# Adafruit_5in_HDMI_Backpack.net
KiCad netlist of a schematic drawn in EAGLE
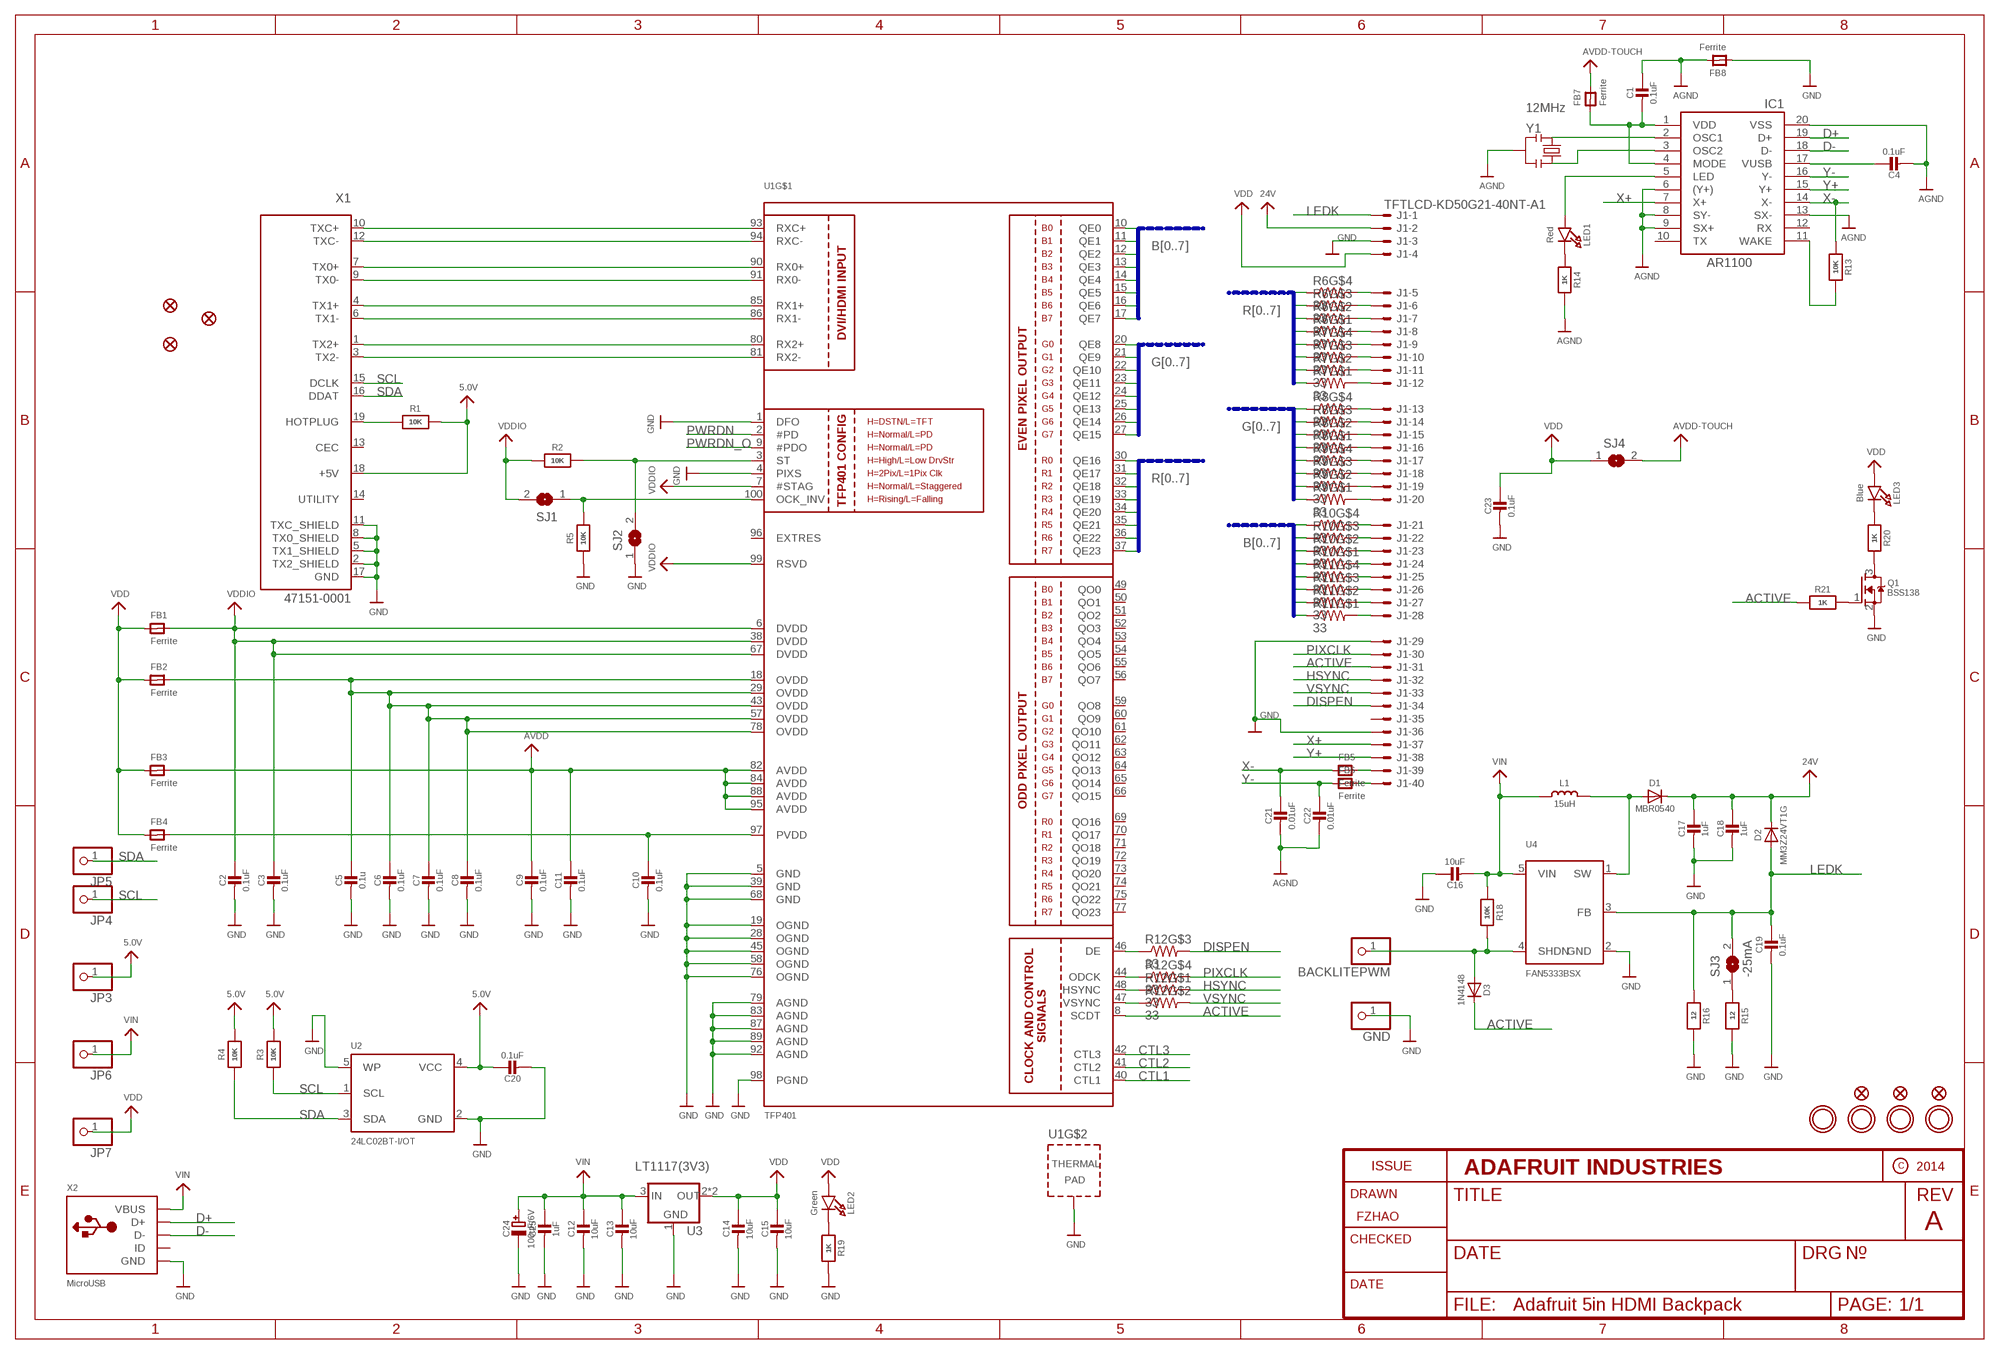
[diagram p0: schematic, sheet 1]

(export (version "E")
  (design (tool "Eeschema 10.0.6"))
  (components
    (comp (ref "BACKLITEPWM")
      (value "HEADER-1X1-SMD_MASKHELD_2X2MM")
      (footprint "eagle-import:1X01_SMD_MASKHELD_2X2MM")
      (libsource (lib "eagle-import") (part "HEADER-1X1-SMD_MASKHELD_2X2MM"))
    )
    (comp (ref "C1")
      (value "0.1uF")
      (footprint "eagle-import:0805-NO")
      (libsource (lib "eagle-import") (part "CAP_CERAMIC0805-NOOUTLINE"))
    )
    (comp (ref "C2")
      (value "0.1uF")
      (footprint "eagle-import:0805-NO")
      (libsource (lib "eagle-import") (part "CAP_CERAMIC0805-NOOUTLINE"))
    )
    (comp (ref "C3")
      (value "0.1uF")
      (footprint "eagle-import:0805-NO")
      (libsource (lib "eagle-import") (part "CAP_CERAMIC0805-NOOUTLINE"))
    )
    (comp (ref "C4")
      (value "0.1uF")
      (footprint "eagle-import:_0805MP")
      (libsource (lib "eagle-import") (part "CAP_CERAMIC_0805MP"))
    )
    (comp (ref "C5")
      (value "0.1u")
      (footprint "eagle-import:0805-NO")
      (libsource (lib "eagle-import") (part "CAP_CERAMIC0805-NOOUTLINE"))
    )
    (comp (ref "C6")
      (value "0.1uF")
      (footprint "eagle-import:_0805MP")
      (libsource (lib "eagle-import") (part "CAP_CERAMIC_0805MP"))
    )
    (comp (ref "C7")
      (value "0.1uF")
      (footprint "eagle-import:0805-NO")
      (libsource (lib "eagle-import") (part "CAP_CERAMIC0805-NOOUTLINE"))
    )
    (comp (ref "C8")
      (value "0.1uF")
      (footprint "eagle-import:0805-NO")
      (libsource (lib "eagle-import") (part "CAP_CERAMIC0805-NOOUTLINE"))
    )
    (comp (ref "C9")
      (value "0.1uF")
      (footprint "eagle-import:0805-NO")
      (libsource (lib "eagle-import") (part "CAP_CERAMIC0805-NOOUTLINE"))
    )
    (comp (ref "C10")
      (value "0.1uF")
      (footprint "eagle-import:0805-NO")
      (libsource (lib "eagle-import") (part "CAP_CERAMIC0805-NOOUTLINE"))
    )
    (comp (ref "C11")
      (value "0.1uF")
      (footprint "eagle-import:0805-NO")
      (libsource (lib "eagle-import") (part "CAP_CERAMIC0805-NOOUTLINE"))
    )
    (comp (ref "C12")
      (value "10uF")
      (footprint "eagle-import:0805-NO")
      (libsource (lib "eagle-import") (part "CAP_CERAMIC0805-NOOUTLINE"))
    )
    (comp (ref "C13")
      (value "10uF")
      (footprint "eagle-import:0805-NO")
      (libsource (lib "eagle-import") (part "CAP_CERAMIC0805-NOOUTLINE"))
    )
    (comp (ref "C14")
      (value "10uF")
      (footprint "eagle-import:0805-NO")
      (libsource (lib "eagle-import") (part "CAP_CERAMIC0805-NOOUTLINE"))
    )
    (comp (ref "C15")
      (value "10uF")
      (footprint "eagle-import:0805-NO")
      (libsource (lib "eagle-import") (part "CAP_CERAMIC0805-NOOUTLINE"))
    )
    (comp (ref "C16")
      (value "10uF")
      (footprint "eagle-import:0805-NO")
      (libsource (lib "eagle-import") (part "CAP_CERAMIC0805-NOOUTLINE"))
    )
    (comp (ref "C17")
      (value "1uF")
      (footprint "eagle-import:0805-NO")
      (libsource (lib "eagle-import") (part "CAP_CERAMIC0805-NOOUTLINE"))
    )
    (comp (ref "C18")
      (value "1uF")
      (footprint "eagle-import:0805-NO")
      (libsource (lib "eagle-import") (part "CAP_CERAMIC0805-NOOUTLINE"))
    )
    (comp (ref "C19")
      (value "0.1uF")
      (footprint "eagle-import:0805-NO")
      (libsource (lib "eagle-import") (part "CAP_CERAMIC0805-NOOUTLINE"))
    )
    (comp (ref "C20")
      (value "0.1uF")
      (footprint "eagle-import:0805-NO")
      (libsource (lib "eagle-import") (part "CAP_CERAMIC0805-NOOUTLINE"))
    )
    (comp (ref "C21")
      (value "0.01uF")
      (footprint "eagle-import:0805-NO")
      (libsource (lib "eagle-import") (part "CAP_CERAMIC0805-NOOUTLINE"))
    )
    (comp (ref "C22")
      (value "0.01uF")
      (footprint "eagle-import:0805-NO")
      (libsource (lib "eagle-import") (part "CAP_CERAMIC0805-NOOUTLINE"))
    )
    (comp (ref "C23")
      (value "0.1uF")
      (footprint "eagle-import:0805-NO")
      (libsource (lib "eagle-import") (part "CAP_CERAMIC0805-NOOUTLINE"))
    )
    (comp (ref "C24")
      (value "100uF/6V")
      (footprint "eagle-import:PANASONIC_C")
      (libsource (lib "eagle-import") (part "CAP_ELECTROLYTICPANASONIC_C"))
    )
    (comp (ref "C25")
      (value "1uF")
      (footprint "eagle-import:0805-NO")
      (libsource (lib "eagle-import") (part "CAP_CERAMIC0805-NOOUTLINE"))
    )
    (comp (ref "D1")
      (value "MBR0540")
      (footprint "eagle-import:SOD-123")
      (libsource (lib "eagle-import") (part "DIODESOD-123"))
    )
    (comp (ref "D2")
      (value "MM3Z24VT1G")
      (footprint "eagle-import:SMADIODE")
      (libsource (lib "eagle-import") (part "DIODESMA"))
    )
    (comp (ref "D3")
      (value "1N4148")
      (footprint "eagle-import:SOD-323")
      (libsource (lib "eagle-import") (part "DIODESOD-323"))
    )
    (comp (ref "FB1")
      (value "Ferrite")
      (footprint "eagle-import:_0805MP")
      (libsource (lib "eagle-import") (part "FERRITE_0805MP"))
    )
    (comp (ref "FB2")
      (value "Ferrite")
      (footprint "eagle-import:_0805MP")
      (libsource (lib "eagle-import") (part "FERRITE_0805MP"))
    )
    (comp (ref "FB3")
      (value "Ferrite")
      (footprint "eagle-import:_0805MP")
      (libsource (lib "eagle-import") (part "FERRITE_0805MP"))
    )
    (comp (ref "FB4")
      (value "Ferrite")
      (footprint "eagle-import:_0805MP")
      (libsource (lib "eagle-import") (part "FERRITE_0805MP"))
    )
    (comp (ref "FB5")
      (value "Ferrite")
      (footprint "eagle-import:_0805MP")
      (libsource (lib "eagle-import") (part "FERRITE_0805MP"))
    )
    (comp (ref "FB6")
      (value "Ferrite")
      (footprint "eagle-import:_0805MP")
      (libsource (lib "eagle-import") (part "FERRITE_0805MP"))
    )
    (comp (ref "FB7")
      (value "Ferrite")
      (footprint "eagle-import:_0805MP")
      (libsource (lib "eagle-import") (part "FERRITE_0805MP"))
    )
    (comp (ref "FB8")
      (value "Ferrite")
      (footprint "eagle-import:_0805MP")
      (libsource (lib "eagle-import") (part "FERRITE_0805MP"))
    )
    (comp (ref "FID1")
      (value "FIDUCIAL\"\"")
      (footprint "eagle-import:FIDUCIAL_1MM")
      (libsource (lib "eagle-import") (part "FIDUCIAL{dblquote}{dblquote}"))
    )
    (comp (ref "FID2")
      (value "FIDUCIAL\"\"")
      (footprint "eagle-import:FIDUCIAL_1MM")
      (libsource (lib "eagle-import") (part "FIDUCIAL{dblquote}{dblquote}"))
    )
    (comp (ref "FID3")
      (value "FIDUCIAL\"\"")
      (footprint "eagle-import:FIDUCIAL_1MM")
      (libsource (lib "eagle-import") (part "FIDUCIAL{dblquote}{dblquote}"))
    )
    (comp (ref "FID4")
      (value "FIDUCIAL\"\"")
      (footprint "eagle-import:FIDUCIAL_1MM")
      (libsource (lib "eagle-import") (part "FIDUCIAL{dblquote}{dblquote}"))
    )
    (comp (ref "FID5")
      (value "FIDUCIAL\"\"")
      (footprint "eagle-import:FIDUCIAL_1MM")
      (libsource (lib "eagle-import") (part "FIDUCIAL{dblquote}{dblquote}"))
    )
    (comp (ref "FID6")
      (value "FIDUCIAL\"\"")
      (footprint "eagle-import:FIDUCIAL_1MM")
      (libsource (lib "eagle-import") (part "FIDUCIAL{dblquote}{dblquote}"))
    )
    (comp (ref "GND")
      (value "HEADER-1X1-SMD_MASKHELD_2X2MM")
      (footprint "eagle-import:1X01_SMD_MASKHELD_2X2MM")
      (libsource (lib "eagle-import") (part "HEADER-1X1-SMD_MASKHELD_2X2MM"))
    )
    (comp (ref "IC1")
      (value "AR1100")
      (footprint "eagle-import:TSSOP20-5.3MMBODY")
      (libsource (lib "eagle-import") (part "AR1100_SSOP"))
    )
    (comp (ref "J1")
      (value "TFTLCD-KD50G21-40NT-A1")
      (footprint "eagle-import:TFTLCD-KD50G21-40NT-A1")
      (libsource (lib "eagle-import") (part "TFTLCD-KD50G21-40NT-A1"))
    )
    (comp (ref "JP3")
      (value "HEADER-1X1-SMD_MASKHELD_2X2MM")
      (footprint "eagle-import:1X01_SMD_MASKHELD_2X2MM")
      (libsource (lib "eagle-import") (part "HEADER-1X1-SMD_MASKHELD_2X2MM"))
    )
    (comp (ref "JP4")
      (value "HEADER-1X1-SMD_MASKHELD_2X2MM")
      (footprint "eagle-import:1X01_SMD_MASKHELD_2X2MM")
      (libsource (lib "eagle-import") (part "HEADER-1X1-SMD_MASKHELD_2X2MM"))
    )
    (comp (ref "JP5")
      (value "HEADER-1X1-SMD_MASKHELD_2X2MM")
      (footprint "eagle-import:1X01_SMD_MASKHELD_2X2MM")
      (libsource (lib "eagle-import") (part "HEADER-1X1-SMD_MASKHELD_2X2MM"))
    )
    (comp (ref "JP6")
      (value "HEADER-1X1-SMD_MASKHELD_2X2MM")
      (footprint "eagle-import:1X01_SMD_MASKHELD_2X2MM")
      (libsource (lib "eagle-import") (part "HEADER-1X1-SMD_MASKHELD_2X2MM"))
    )
    (comp (ref "JP7")
      (value "HEADER-1X1-SMD_MASKHELD_2X2MM")
      (footprint "eagle-import:1X01_SMD_MASKHELD_2X2MM")
      (libsource (lib "eagle-import") (part "HEADER-1X1-SMD_MASKHELD_2X2MM"))
    )
    (comp (ref "L1")
      (value "15uH")
      (footprint "eagle-import:INDUCTOR_5X5MM_NR5040_NOTHERMALS")
      (libsource (lib "eagle-import") (part "INDUCTORNR5040"))
    )
    (comp (ref "LED1")
      (value "Red")
      (footprint "eagle-import:CHIPLED_0805_NOOUTLINE")
      (libsource (lib "eagle-import") (part "LED0805_NOOUTLINE"))
    )
    (comp (ref "LED2")
      (value "Green")
      (footprint "eagle-import:CHIPLED_0805_NOOUTLINE")
      (libsource (lib "eagle-import") (part "LED0805_NOOUTLINE"))
    )
    (comp (ref "LED3")
      (value "Blue")
      (footprint "eagle-import:CHIPLED_0805_NOOUTLINE")
      (libsource (lib "eagle-import") (part "LED0805_NOOUTLINE"))
    )
    (comp (ref "Q1")
      (value "BSS138")
      (footprint "eagle-import:SOT23-WIDE")
      (libsource (lib "eagle-import") (part "MOSFET-NWIDE"))
    )
    (comp (ref "R1")
      (value "10K")
      (footprint "eagle-import:0805-NO")
      (libsource (lib "eagle-import") (part "RESISTOR0805_NOOUTLINE"))
    )
    (comp (ref "R2")
      (value "10K")
      (footprint "eagle-import:_0805MP")
      (libsource (lib "eagle-import") (part "RESISTOR_0805MP"))
    )
    (comp (ref "R3")
      (value "10K")
      (footprint "eagle-import:0805-NO")
      (libsource (lib "eagle-import") (part "RESISTOR0805_NOOUTLINE"))
    )
    (comp (ref "R4")
      (value "10K")
      (footprint "eagle-import:0805-NO")
      (libsource (lib "eagle-import") (part "RESISTOR0805_NOOUTLINE"))
    )
    (comp (ref "R5")
      (value "10K")
      (footprint "eagle-import:_0805MP")
      (libsource (lib "eagle-import") (part "RESISTOR_0805MP"))
    )
    (comp (ref "R6")
      (value "33")
      (footprint "eagle-import:RESPACK_4X0603")
      (libsource (lib "eagle-import") (part "RESISTOR_4PACK_US"))
    )
    (comp (ref "R7")
      (value "33")
      (footprint "eagle-import:RESPACK_4X0603")
      (libsource (lib "eagle-import") (part "RESISTOR_4PACK_US"))
    )
    (comp (ref "R8")
      (value "33")
      (footprint "eagle-import:RESPACK_4X0603")
      (libsource (lib "eagle-import") (part "RESISTOR_4PACK_US"))
    )
    (comp (ref "R9")
      (value "33")
      (footprint "eagle-import:RESPACK_4X0603")
      (libsource (lib "eagle-import") (part "RESISTOR_4PACK_US"))
    )
    (comp (ref "R10")
      (value "33")
      (footprint "eagle-import:RESPACK_4X0603")
      (libsource (lib "eagle-import") (part "RESISTOR_4PACK_US"))
    )
    (comp (ref "R11")
      (value "33")
      (footprint "eagle-import:RESPACK_4X0603")
      (libsource (lib "eagle-import") (part "RESISTOR_4PACK_US"))
    )
    (comp (ref "R12")
      (value "33")
      (footprint "eagle-import:RESPACK_4X0603")
      (libsource (lib "eagle-import") (part "RESISTOR_4PACK_US"))
    )
    (comp (ref "R13")
      (value "10K")
      (footprint "eagle-import:0805-NO")
      (libsource (lib "eagle-import") (part "RESISTOR0805_NOOUTLINE"))
    )
    (comp (ref "R14")
      (value "1K")
      (footprint "eagle-import:0805-NO")
      (libsource (lib "eagle-import") (part "RESISTOR0805_NOOUTLINE"))
    )
    (comp (ref "R15")
      (value "12")
      (footprint "eagle-import:0805-NO")
      (libsource (lib "eagle-import") (part "RESISTOR0805_NOOUTLINE"))
    )
    (comp (ref "R16")
      (value "12")
      (footprint "eagle-import:0805-NO")
      (libsource (lib "eagle-import") (part "RESISTOR0805_NOOUTLINE"))
    )
    (comp (ref "R18")
      (value "10K")
      (footprint "eagle-import:0805-NO")
      (libsource (lib "eagle-import") (part "RESISTOR0805_NOOUTLINE"))
    )
    (comp (ref "R19")
      (value "1K")
      (footprint "eagle-import:0805-NO")
      (libsource (lib "eagle-import") (part "RESISTOR0805_NOOUTLINE"))
    )
    (comp (ref "R20")
      (value "1K")
      (footprint "eagle-import:0805-NO")
      (libsource (lib "eagle-import") (part "RESISTOR0805_NOOUTLINE"))
    )
    (comp (ref "R21")
      (value "1K")
      (footprint "eagle-import:0805-NO")
      (libsource (lib "eagle-import") (part "RESISTOR0805_NOOUTLINE"))
    )
    (comp (ref "SJ1")
      (value "SOLDERJUMPER")
      (footprint "eagle-import:SOLDERJUMPER_ARROW_NOPASTE")
      (libsource (lib "eagle-import") (part "SOLDERJUMPER"))
    )
    (comp (ref "SJ2")
      (value "SOLDERJUMPER")
      (footprint "eagle-import:SOLDERJUMPER_ARROW_NOPASTE")
      (fields (field (name "BOM") "EXCLUDE"))
      (libsource (lib "eagle-import") (part "SOLDERJUMPER"))
    )
    (comp (ref "SJ3")
      (value "-25mA")
      (footprint "eagle-import:SOLDERJUMPER_CLOSEDWIRE")
      (libsource (lib "eagle-import") (part "SOLDERJUMPERCLOSED"))
    )
    (comp (ref "SJ4")
      (value "SOLDERJUMPERCLOSED")
      (footprint "eagle-import:SOLDERJUMPER_CLOSEDWIRE")
      (libsource (lib "eagle-import") (part "SOLDERJUMPERCLOSED"))
    )
    (comp (ref "U$31")
      (value "MOUNTINGHOLE3.0")
      (footprint "eagle-import:MOUNTINGHOLE_3.0_PLATED")
      (libsource (lib "eagle-import") (part "MOUNTINGHOLE3.0"))
    )
    (comp (ref "U$32")
      (value "MOUNTINGHOLE3.0")
      (footprint "eagle-import:MOUNTINGHOLE_3.0_PLATED")
      (libsource (lib "eagle-import") (part "MOUNTINGHOLE3.0"))
    )
    (comp (ref "U$33")
      (value "MOUNTINGHOLE3.0")
      (footprint "eagle-import:MOUNTINGHOLE_3.0_PLATED")
      (libsource (lib "eagle-import") (part "MOUNTINGHOLE3.0"))
    )
    (comp (ref "U$34")
      (value "MOUNTINGHOLE3.0")
      (footprint "eagle-import:MOUNTINGHOLE_3.0_PLATED")
      (libsource (lib "eagle-import") (part "MOUNTINGHOLE3.0"))
    )
    (comp (ref "U1")
      (value "TFP401")
      (footprint "eagle-import:S-PQFP-G100")
      (libsource (lib "eagle-import") (part "TFP401"))
    )
    (comp (ref "U2")
      (value "24LC02BT-I/OT")
      (footprint "eagle-import:SOT23-5")
      (libsource (lib "eagle-import") (part "EEPROM_I2C_MCP24AA32"))
    )
    (comp (ref "U3")
      (value "LT1117(3V3)")
      (footprint "eagle-import:SOT223-R")
      (libsource (lib "eagle-import") (part "VREG_SOT223"))
    )
    (comp (ref "U4")
      (value "FAN5333BSX")
      (footprint "eagle-import:SOT23-5")
      (libsource (lib "eagle-import") (part "VREG_FAN5331"))
    )
    (comp (ref "X1")
      (value "47151-0001")
      (footprint "eagle-import:HDMI_MOLEX_47151-0001_DIMLAYER")
      (libsource (lib "eagle-import") (part "HDMI_MOLEX_47151DIM"))
    )
    (comp (ref "X2")
      (value "MicroUSB")
      (footprint "eagle-import:4UCONN_20329")
      (libsource (lib "eagle-import") (part "USBMICRO_20329"))
    )
    (comp (ref "Y1")
      (value "12MHz")
      (footprint "eagle-import:RESONATOR-SMD")
      (libsource (lib "eagle-import") (part "RESONATORSMD"))
    )
  )
  (nets
    (net (code "1") (name "/ACTIVE") (class "Default")
      (node (ref "D3") (pin "C") (pinfunction "C_C") (pintype "passive"))
      (node (ref "J1") (pin "31") (pinfunction "MS_31") (pintype "passive"))
      (node (ref "R21") (pin "1") (pinfunction "1_1") (pintype "passive"))
      (node (ref "U1") (pin "8") (pinfunction "SCDT_8") (pintype "output"))
    )
    (net (code "2") (name "/B0") (class "Default")
      (node (ref "R10") (pin "4") (pinfunction "1_4") (pintype "passive"))
      (node (ref "U1") (pin "10") (pinfunction "QE0_10") (pintype "output"))
    )
    (net (code "3") (name "/B1") (class "Default")
      (node (ref "R10") (pin "3") (pinfunction "1_3") (pintype "passive"))
      (node (ref "U1") (pin "11") (pinfunction "QE1_11") (pintype "output"))
    )
    (net (code "4") (name "/B2") (class "Default")
      (node (ref "R10") (pin "2") (pinfunction "1_2") (pintype "passive"))
      (node (ref "U1") (pin "12") (pinfunction "QE2_12") (pintype "output"))
    )
    (net (code "5") (name "/B3") (class "Default")
      (node (ref "R10") (pin "1") (pinfunction "1_1") (pintype "passive"))
      (node (ref "U1") (pin "13") (pinfunction "QE3_13") (pintype "output"))
    )
    (net (code "6") (name "/B4") (class "Default")
      (node (ref "R11") (pin "4") (pinfunction "1_4") (pintype "passive"))
      (node (ref "U1") (pin "14") (pinfunction "QE4_14") (pintype "output"))
    )
    (net (code "7") (name "/B5") (class "Default")
      (node (ref "R11") (pin "3") (pinfunction "1_3") (pintype "passive"))
      (node (ref "U1") (pin "15") (pinfunction "QE5_15") (pintype "output"))
    )
    (net (code "8") (name "/B6") (class "Default")
      (node (ref "R11") (pin "2") (pinfunction "1_2") (pintype "passive"))
      (node (ref "U1") (pin "16") (pinfunction "QE6_16") (pintype "output"))
    )
    (net (code "9") (name "/B7") (class "Default")
      (node (ref "R11") (pin "1") (pinfunction "1_1") (pintype "passive"))
      (node (ref "U1") (pin "17") (pinfunction "QE7_17") (pintype "output"))
    )
    (net (code "11") (name "/CTL1") (class "Default")
      (node (ref "U1") (pin "40") (pinfunction "CTL1_40") (pintype "output"))
    )
    (net (code "12") (name "/CTL2") (class "Default")
      (node (ref "U1") (pin "41") (pinfunction "CTL2_41") (pintype "output"))
    )
    (net (code "13") (name "/CTL3") (class "Default")
      (node (ref "U1") (pin "42") (pinfunction "CTL3_42") (pintype "output"))
    )
    (net (code "14") (name "/D+") (class "Default")
      (node (ref "IC1") (pin "19") (pinfunction "D+_19") (pintype "bidirectional"))
      (node (ref "X2") (pin "D+") (pinfunction "D+_D+") (pintype "bidirectional"))
    )
    (net (code "15") (name "/D-") (class "Default")
      (node (ref "IC1") (pin "18") (pinfunction "D-_18") (pintype "bidirectional"))
      (node (ref "X2") (pin "D-") (pinfunction "D-_D-") (pintype "bidirectional"))
    )
    (net (code "16") (name "/DISPEN") (class "Default")
      (node (ref "J1") (pin "34") (pinfunction "MS_34") (pintype "passive"))
      (node (ref "R12") (pin "6") (pinfunction "2_6") (pintype "passive"))
    )
    (net (code "17") (name "/G0") (class "Default")
      (node (ref "R8") (pin "4") (pinfunction "1_4") (pintype "passive"))
      (node (ref "U1") (pin "20") (pinfunction "QE8_20") (pintype "output"))
    )
    (net (code "18") (name "/G1") (class "Default")
      (node (ref "R8") (pin "3") (pinfunction "1_3") (pintype "passive"))
      (node (ref "U1") (pin "21") (pinfunction "QE9_21") (pintype "output"))
    )
    (net (code "19") (name "/G2") (class "Default")
      (node (ref "R8") (pin "2") (pinfunction "1_2") (pintype "passive"))
      (node (ref "U1") (pin "22") (pinfunction "QE10_22") (pintype "output"))
    )
    (net (code "20") (name "/G3") (class "Default")
      (node (ref "R8") (pin "1") (pinfunction "1_1") (pintype "passive"))
      (node (ref "U1") (pin "23") (pinfunction "QE11_23") (pintype "output"))
    )
    (net (code "21") (name "/G4") (class "Default")
      (node (ref "R9") (pin "4") (pinfunction "1_4") (pintype "passive"))
      (node (ref "U1") (pin "24") (pinfunction "QE12_24") (pintype "output"))
    )
    (net (code "22") (name "/G5") (class "Default")
      (node (ref "R9") (pin "3") (pinfunction "1_3") (pintype "passive"))
      (node (ref "U1") (pin "25") (pinfunction "QE13_25") (pintype "output"))
    )
    (net (code "23") (name "/G6") (class "Default")
      (node (ref "R9") (pin "2") (pinfunction "1_2") (pintype "passive"))
      (node (ref "U1") (pin "26") (pinfunction "QE14_26") (pintype "output"))
    )
    (net (code "24") (name "/G7") (class "Default")
      (node (ref "R9") (pin "1") (pinfunction "1_1") (pintype "passive"))
      (node (ref "U1") (pin "27") (pinfunction "QE15_27") (pintype "output"))
    )
    (net (code "26") (name "/HSYNC") (class "Default")
      (node (ref "J1") (pin "32") (pinfunction "MS_32") (pintype "passive"))
      (node (ref "R12") (pin "8") (pinfunction "2_8") (pintype "passive"))
    )
    (net (code "27") (name "/LEDK") (class "Default")
      (node (ref "C19") (pin "1") (pinfunction "1_1") (pintype "passive"))
      (node (ref "D2") (pin "A") (pinfunction "A_A") (pintype "passive"))
      (node (ref "J1") (pin "1") (pinfunction "MSV_1") (pintype "passive"))
      (node (ref "R16") (pin "1") (pinfunction "1_1") (pintype "passive"))
      (node (ref "SJ3") (pin "2") (pinfunction "2_2") (pintype "passive"))
      (node (ref "U4") (pin "3") (pinfunction "FB_3") (pintype "bidirectional"))
    )
    (net (code "28") (name "/PIXCLK") (class "Default")
      (node (ref "J1") (pin "30") (pinfunction "MS_30") (pintype "passive"))
      (node (ref "R12") (pin "5") (pinfunction "2_5") (pintype "passive"))
    )
    (net (code "29") (name "/PWRDN") (class "Default")
      (node (ref "U1") (pin "2") (pinfunction "#PD_2") (pintype "input"))
    )
    (net (code "30") (name "/PWRDN_O") (class "Default")
      (node (ref "U1") (pin "9") (pinfunction "#PDO_9") (pintype "input"))
    )
    (net (code "31") (name "/R0") (class "Default")
      (node (ref "R6") (pin "4") (pinfunction "1_4") (pintype "passive"))
      (node (ref "U1") (pin "30") (pinfunction "QE16_30") (pintype "output"))
    )
    (net (code "32") (name "/R1") (class "Default")
      (node (ref "R6") (pin "3") (pinfunction "1_3") (pintype "passive"))
      (node (ref "U1") (pin "31") (pinfunction "QE17_31") (pintype "output"))
    )
    (net (code "33") (name "/R2") (class "Default")
      (node (ref "R6") (pin "2") (pinfunction "1_2") (pintype "passive"))
      (node (ref "U1") (pin "32") (pinfunction "QE18_32") (pintype "output"))
    )
    (net (code "34") (name "/R3") (class "Default")
      (node (ref "R6") (pin "1") (pinfunction "1_1") (pintype "passive"))
      (node (ref "U1") (pin "33") (pinfunction "QE19_33") (pintype "output"))
    )
    (net (code "35") (name "/R4") (class "Default")
      (node (ref "R7") (pin "4") (pinfunction "1_4") (pintype "passive"))
      (node (ref "U1") (pin "34") (pinfunction "QE20_34") (pintype "output"))
    )
    (net (code "36") (name "/R5") (class "Default")
      (node (ref "R7") (pin "3") (pinfunction "1_3") (pintype "passive"))
      (node (ref "U1") (pin "35") (pinfunction "QE21_35") (pintype "output"))
    )
    (net (code "37") (name "/R6") (class "Default")
      (node (ref "R7") (pin "2") (pinfunction "1_2") (pintype "passive"))
      (node (ref "U1") (pin "36") (pinfunction "QE22_36") (pintype "output"))
    )
    (net (code "38") (name "/R7") (class "Default")
      (node (ref "R7") (pin "1") (pinfunction "1_1") (pintype "passive"))
      (node (ref "U1") (pin "37") (pinfunction "QE23_37") (pintype "output"))
    )
    (net (code "40") (name "/SCL") (class "Default")
      (node (ref "JP4") (pin "1") (pinfunction "1_1") (pintype "passive"))
      (node (ref "R3") (pin "1") (pinfunction "1_1") (pintype "passive"))
      (node (ref "U2") (pin "1") (pinfunction "SCL_1") (pintype "bidirectional"))
      (node (ref "X1") (pin "15") (pinfunction "DCLK_15") (pintype "bidirectional"))
    )
    (net (code "41") (name "/SDA") (class "Default")
      (node (ref "JP5") (pin "1") (pinfunction "1_1") (pintype "passive"))
      (node (ref "R4") (pin "1") (pinfunction "1_1") (pintype "passive"))
      (node (ref "U2") (pin "3") (pinfunction "SDA_3") (pintype "bidirectional"))
      (node (ref "X1") (pin "16") (pinfunction "DDAT_16") (pintype "bidirectional"))
    )
    (net (code "42") (name "/VSYNC") (class "Default")
      (node (ref "J1") (pin "33") (pinfunction "MS_33") (pintype "passive"))
      (node (ref "R12") (pin "7") (pinfunction "2_7") (pintype "passive"))
    )
    (net (code "43") (name "/X+") (class "Default")
      (node (ref "IC1") (pin "7") (pinfunction "X+_7") (pintype "bidirectional"))
      (node (ref "J1") (pin "37") (pinfunction "MS_37") (pintype "passive"))
    )
    (net (code "44") (name "/X-") (class "Default")
      (node (ref "C21") (pin "1") (pinfunction "1_1") (pintype "passive"))
      (node (ref "FB5") (pin "1") (pinfunction "P$1_1") (pintype "passive"))
      (node (ref "IC1") (pin "14") (pinfunction "X-_14") (pintype "bidirectional"))
      (node (ref "R13") (pin "1") (pinfunction "1_1") (pintype "passive"))
    )
    (net (code "45") (name "/Y+") (class "Default")
      (node (ref "IC1") (pin "15") (pinfunction "Y+_15") (pintype "bidirectional"))
      (node (ref "J1") (pin "38") (pinfunction "MS_38") (pintype "passive"))
    )
    (net (code "46") (name "/Y-") (class "Default")
      (node (ref "C22") (pin "1") (pinfunction "1_1") (pintype "passive"))
      (node (ref "FB6") (pin "1") (pinfunction "P$1_1") (pintype "passive"))
      (node (ref "IC1") (pin "16") (pinfunction "Y-_16") (pintype "bidirectional"))
    )
    (net (code "47") (name "5.0V") (class "Default")
      (node (ref "C20") (pin "1") (pinfunction "1_1") (pintype "passive"))
      (node (ref "JP3") (pin "1") (pinfunction "1_1") (pintype "passive"))
      (node (ref "R1") (pin "2") (pinfunction "2_2") (pintype "passive"))
      (node (ref "R3") (pin "2") (pinfunction "2_2") (pintype "passive"))
      (node (ref "R4") (pin "2") (pinfunction "2_2") (pintype "passive"))
      (node (ref "U2") (pin "4") (pinfunction "VCC_4") (pintype "bidirectional"))
      (node (ref "X1") (pin "18") (pinfunction "+5V_18") (pintype "power_in"))
    )
    (net (code "48") (name "24V") (class "Default")
      (node (ref "C17") (pin "1") (pinfunction "1_1") (pintype "passive"))
      (node (ref "C18") (pin "1") (pinfunction "1_1") (pintype "passive"))
      (node (ref "D1") (pin "C") (pinfunction "C_C") (pintype "passive"))
      (node (ref "D2") (pin "C") (pinfunction "C_C") (pintype "passive"))
      (node (ref "J1") (pin "2") (pinfunction "MS_2") (pintype "passive"))
    )
    (net (code "49") (name "AGND") (class "Default")
      (node (ref "C1") (pin "1") (pinfunction "1_1") (pintype "passive"))
      (node (ref "C21") (pin "2") (pinfunction "2_2") (pintype "passive"))
      (node (ref "C22") (pin "2") (pinfunction "2_2") (pintype "passive"))
      (node (ref "C4") (pin "2") (pinfunction "2_2") (pintype "passive"))
      (node (ref "FB8") (pin "2") (pinfunction "P$2_2") (pintype "passive"))
      (node (ref "IC1") (pin "13") (pinfunction "SX-_13") (pintype "bidirectional"))
      (node (ref "IC1") (pin "20") (pinfunction "VSS_20") (pintype "power_in"))
      (node (ref "IC1") (pin "6") (pinfunction "(Y+)_6") (pintype "bidirectional"))
      (node (ref "IC1") (pin "8") (pinfunction "SY-_8") (pintype "bidirectional"))
      (node (ref "IC1") (pin "9") (pinfunction "SX+_9") (pintype "bidirectional"))
      (node (ref "R14") (pin "2") (pinfunction "2_2") (pintype "passive"))
      (node (ref "Y1") (pin "2") (pinfunction "2_2") (pintype "passive"))
    )
    (net (code "50") (name "AVDD") (class "Default")
      (node (ref "C11") (pin "1") (pinfunction "1_1") (pintype "passive"))
      (node (ref "C9") (pin "1") (pinfunction "1_1") (pintype "passive"))
      (node (ref "FB3") (pin "2") (pinfunction "P$2_2") (pintype "passive"))
      (node (ref "U1") (pin "82") (pinfunction "AVDD_82") (pintype "power_in"))
      (node (ref "U1") (pin "84") (pinfunction "AVDD_84") (pintype "power_in"))
      (node (ref "U1") (pin "88") (pinfunction "AVDD_88") (pintype "power_in"))
      (node (ref "U1") (pin "95") (pinfunction "AVDD_95") (pintype "power_in"))
    )
    (net (code "51") (name "AVDD-TOUCH") (class "Default")
      (node (ref "FB7") (pin "2") (pinfunction "P$2_2") (pintype "passive"))
      (node (ref "SJ4") (pin "2") (pinfunction "2_2") (pintype "passive"))
    )
    (net (code "52") (name "GND") (class "Default")
      (node (ref "C10") (pin "2") (pinfunction "2_2") (pintype "passive"))
      (node (ref "C11") (pin "2") (pinfunction "2_2") (pintype "passive"))
      (node (ref "C12") (pin "2") (pinfunction "2_2") (pintype "passive"))
      (node (ref "C13") (pin "2") (pinfunction "2_2") (pintype "passive"))
      (node (ref "C14") (pin "2") (pinfunction "2_2") (pintype "passive"))
      (node (ref "C15") (pin "2") (pinfunction "2_2") (pintype "passive"))
      (node (ref "C16") (pin "1") (pinfunction "1_1") (pintype "passive"))
      (node (ref "C17") (pin "2") (pinfunction "2_2") (pintype "passive"))
      (node (ref "C18") (pin "2") (pinfunction "2_2") (pintype "passive"))
      (node (ref "C19") (pin "2") (pinfunction "2_2") (pintype "passive"))
      (node (ref "C2") (pin "2") (pinfunction "2_2") (pintype "passive"))
      (node (ref "C20") (pin "2") (pinfunction "2_2") (pintype "passive"))
      (node (ref "C23") (pin "2") (pinfunction "2_2") (pintype "passive"))
      (node (ref "C24") (pin "-") (pinfunction "-_-") (pintype "passive"))
      (node (ref "C25") (pin "2") (pinfunction "2_2") (pintype "passive"))
      (node (ref "C3") (pin "2") (pinfunction "2_2") (pintype "passive"))
      (node (ref "C5") (pin "2") (pinfunction "2_2") (pintype "passive"))
      (node (ref "C6") (pin "2") (pinfunction "2_2") (pintype "passive"))
      (node (ref "C7") (pin "2") (pinfunction "2_2") (pintype "passive"))
      (node (ref "C8") (pin "2") (pinfunction "2_2") (pintype "passive"))
      (node (ref "C9") (pin "2") (pinfunction "2_2") (pintype "passive"))
      (node (ref "FB8") (pin "1") (pinfunction "P$1_1") (pintype "passive"))
      (node (ref "GND") (pin "1") (pinfunction "1_1") (pintype "passive"))
      (node (ref "J1") (pin "29") (pinfunction "MS_29") (pintype "passive"))
      (node (ref "J1") (pin "3") (pinfunction "MS_3") (pintype "passive"))
      (node (ref "J1") (pin "36") (pinfunction "MS_36") (pintype "passive"))
      (node (ref "Q1") (pin "2") (pinfunction "S_2") (pintype "bidirectional"))
      (node (ref "R15") (pin "2") (pinfunction "2_2") (pintype "passive"))
      (node (ref "R16") (pin "2") (pinfunction "2_2") (pintype "passive"))
      (node (ref "R19") (pin "2") (pinfunction "2_2") (pintype "passive"))
      (node (ref "R5") (pin "1") (pinfunction "1_1") (pintype "passive"))
      (node (ref "SJ2") (pin "1") (pinfunction "1_1") (pintype "passive"))
      (node (ref "U1") (pin "1") (pinfunction "DFO_1") (pintype "input"))
      (node (ref "U1") (pin "19") (pinfunction "OGND_19") (pintype "power_in"))
      (node (ref "U1") (pin "28") (pinfunction "OGND_28") (pintype "power_in"))
      (node (ref "U1") (pin "39") (pinfunction "GND_39") (pintype "power_in"))
      (node (ref "U1") (pin "4") (pinfunction "PIXS_4") (pintype "input"))
      (node (ref "U1") (pin "45") (pinfunction "OGND_45") (pintype "power_in"))
      (node (ref "U1") (pin "5") (pinfunction "GND_5") (pintype "power_in"))
      (node (ref "U1") (pin "58") (pinfunction "OGND_58") (pintype "power_in"))
      (node (ref "U1") (pin "68") (pinfunction "GND_68") (pintype "power_in"))
      (node (ref "U1") (pin "76") (pinfunction "OGND_76") (pintype "power_in"))
      (node (ref "U1") (pin "79") (pinfunction "AGND_79") (pintype "power_in"))
      (node (ref "U1") (pin "83") (pinfunction "AGND_83") (pintype "power_in"))
      (node (ref "U1") (pin "87") (pinfunction "AGND_87") (pintype "power_in"))
      (node (ref "U1") (pin "89") (pinfunction "AGND_89") (pintype "power_in"))
      (node (ref "U1") (pin "92") (pinfunction "AGND_92") (pintype "power_in"))
      (node (ref "U1") (pin "98") (pinfunction "PGND_98") (pintype "power_in"))
      (node (ref "U1") (pin "P$1") (pinfunction "TP_P$1") (pintype "power_in"))
      (node (ref "U1") (pin "P$10") (pinfunction "TP_P$10") (pintype "power_in"))
      (node (ref "U1") (pin "P$11") (pinfunction "TP_P$11") (pintype "power_in"))
      (node (ref "U1") (pin "P$12") (pinfunction "TP_P$12") (pintype "power_in"))
      (node (ref "U1") (pin "P$13") (pinfunction "TP_P$13") (pintype "power_in"))
      (node (ref "U1") (pin "P$14") (pinfunction "TP_P$14") (pintype "power_in"))
      (node (ref "U1") (pin "P$15") (pinfunction "TP_P$15") (pintype "power_in"))
      (node (ref "U1") (pin "P$16") (pinfunction "TP_P$16") (pintype "power_in"))
      (node (ref "U1") (pin "P$2") (pinfunction "TP_P$2") (pintype "power_in"))
      (node (ref "U1") (pin "P$3") (pinfunction "TP_P$3") (pintype "power_in"))
      (node (ref "U1") (pin "P$4") (pinfunction "TP_P$4") (pintype "power_in"))
      (node (ref "U1") (pin "P$5") (pinfunction "TP_P$5") (pintype "power_in"))
      (node (ref "U1") (pin "P$6") (pinfunction "TP_P$6") (pintype "power_in"))
      (node (ref "U1") (pin "P$7") (pinfunction "TP_P$7") (pintype "power_in"))
      (node (ref "U1") (pin "P$8") (pinfunction "TP_P$8") (pintype "power_in"))
      (node (ref "U1") (pin "P$9") (pinfunction "TP_P$9") (pintype "power_in"))
      (node (ref "U1") (pin "THERMAL") (pinfunction "TP_THERMAL") (pintype "power_in"))
      (node (ref "U2") (pin "2") (pinfunction "GND_2") (pintype "bidirectional"))
      (node (ref "U2") (pin "5") (pinfunction "WP_5") (pintype "bidirectional"))
      (node (ref "U3") (pin "1") (pinfunction "GND_1") (pintype "power_in"))
      (node (ref "U4") (pin "2") (pinfunction "GND_2") (pintype "bidirectional"))
      (node (ref "X1") (pin "11") (pinfunction "TXC_SHIELD_11") (pintype "power_in"))
      (node (ref "X1") (pin "17") (pinfunction "GND_17") (pintype "power_in"))
      (node (ref "X1") (pin "2") (pinfunction "TX2_SHIELD_2") (pintype "power_in"))
      (node (ref "X1") (pin "5") (pinfunction "TX1_SHIELD_5") (pintype "power_in"))
      (node (ref "X1") (pin "8") (pinfunction "TX0_SHIELD_8") (pintype "power_in"))
      (node (ref "X2") (pin "BASE@1") (pinfunction "GND_BASE@1") (pintype "power_in"))
      (node (ref "X2") (pin "BASE@2") (pinfunction "GND_BASE@2") (pintype "power_in"))
      (node (ref "X2") (pin "GND") (pinfunction "GND_GND") (pintype "power_in"))
      (node (ref "X2") (pin "SPRT@1") (pinfunction "GND_SPRT@1") (pintype "power_in"))
      (node (ref "X2") (pin "SPRT@2") (pinfunction "GND_SPRT@2") (pintype "power_in"))
      (node (ref "X2") (pin "SPRT@3") (pinfunction "GND_SPRT@3") (pintype "power_in"))
      (node (ref "X2") (pin "SPRT@4") (pinfunction "GND_SPRT@4") (pintype "power_in"))
    )
    (net (code "53") (name "Net-(FB2-P$2)") (class "Default")
      (node (ref "C5") (pin "1") (pinfunction "1_1") (pintype "passive"))
      (node (ref "C6") (pin "1") (pinfunction "1_1") (pintype "passive"))
      (node (ref "C7") (pin "1") (pinfunction "1_1") (pintype "passive"))
      (node (ref "C8") (pin "1") (pinfunction "1_1") (pintype "passive"))
      (node (ref "FB2") (pin "2") (pinfunction "P$2_2") (pintype "passive"))
      (node (ref "U1") (pin "18") (pinfunction "OVDD_18") (pintype "power_in"))
      (node (ref "U1") (pin "29") (pinfunction "OVDD_29") (pintype "power_in"))
      (node (ref "U1") (pin "43") (pinfunction "OVDD_43") (pintype "power_in"))
      (node (ref "U1") (pin "57") (pinfunction "OVDD_57") (pintype "power_in"))
      (node (ref "U1") (pin "78") (pinfunction "OVDD_78") (pintype "power_in"))
    )
    (net (code "54") (name "Net-(FB4-P$2)") (class "Default")
      (node (ref "C10") (pin "1") (pinfunction "1_1") (pintype "passive"))
      (node (ref "FB4") (pin "2") (pinfunction "P$2_2") (pintype "passive"))
      (node (ref "U1") (pin "97") (pinfunction "PVDD_97") (pintype "power_in"))
    )
    (net (code "55") (name "Net-(FB5-P$2)") (class "Default")
      (node (ref "FB5") (pin "2") (pinfunction "P$2_2") (pintype "passive"))
      (node (ref "J1") (pin "39") (pinfunction "MS_39") (pintype "passive"))
    )
    (net (code "56") (name "Net-(FB6-P$2)") (class "Default")
      (node (ref "FB6") (pin "2") (pinfunction "P$2_2") (pintype "passive"))
      (node (ref "J1") (pin "40") (pinfunction "MS_40") (pintype "passive"))
    )
    (net (code "57") (name "Net-(FB7-P$1)") (class "Default")
      (node (ref "C1") (pin "2") (pinfunction "2_2") (pintype "passive"))
      (node (ref "FB7") (pin "1") (pinfunction "P$1_1") (pintype "passive"))
      (node (ref "IC1") (pin "1") (pinfunction "VDD_1") (pintype "power_in"))
      (node (ref "IC1") (pin "4") (pinfunction "MODE_4") (pintype "input"))
    )
    (net (code "58") (name "Net-(IC1-LED)") (class "Default")
      (node (ref "IC1") (pin "5") (pinfunction "LED_5") (pintype "output"))
      (node (ref "LED1") (pin "A") (pinfunction "A_A") (pintype "passive"))
    )
    (net (code "59") (name "Net-(IC1-OSC1)") (class "Default")
      (node (ref "IC1") (pin "2") (pinfunction "OSC1_2") (pintype "passive"))
      (node (ref "Y1") (pin "1") (pinfunction "1_1") (pintype "passive"))
    )
    (net (code "60") (name "Net-(IC1-OSC2)") (class "Default")
      (node (ref "IC1") (pin "3") (pinfunction "OSC2_3") (pintype "passive"))
      (node (ref "Y1") (pin "3") (pinfunction "3_3") (pintype "passive"))
    )
    (net (code "61") (name "Net-(IC1-VUSB)") (class "Default")
      (node (ref "C4") (pin "1") (pinfunction "1_1") (pintype "passive"))
      (node (ref "IC1") (pin "17") (pinfunction "VUSB_17") (pintype "power_in"))
    )
    (net (code "62") (name "Net-(IC1-WAKE)") (class "Default")
      (node (ref "IC1") (pin "11") (pinfunction "WAKE_11") (pintype "input"))
      (node (ref "R13") (pin "2") (pinfunction "2_2") (pintype "passive"))
    )
    (net (code "63") (name "Net-(J1AJ-MS)") (class "Default")
      (node (ref "J1") (pin "5") (pinfunction "MS_5") (pintype "passive"))
      (node (ref "R6") (pin "5") (pinfunction "2_5") (pintype "passive"))
    )
    (net (code "64") (name "Net-(J1AK-MS)") (class "Default")
      (node (ref "J1") (pin "6") (pinfunction "MS_6") (pintype "passive"))
      (node (ref "R6") (pin "6") (pinfunction "2_6") (pintype "passive"))
    )
    (net (code "65") (name "Net-(J1AL-MS)") (class "Default")
      (node (ref "J1") (pin "7") (pinfunction "MS_7") (pintype "passive"))
      (node (ref "R6") (pin "7") (pinfunction "2_7") (pintype "passive"))
    )
    (net (code "66") (name "Net-(J1AM-MS)") (class "Default")
      (node (ref "J1") (pin "8") (pinfunction "MS_8") (pintype "passive"))
      (node (ref "R6") (pin "8") (pinfunction "2_8") (pintype "passive"))
    )
    (net (code "67") (name "Net-(J1AN-MS)") (class "Default")
      (node (ref "J1") (pin "9") (pinfunction "MS_9") (pintype "passive"))
      (node (ref "R7") (pin "5") (pinfunction "2_5") (pintype "passive"))
    )
    (net (code "68") (name "Net-(J1B-MS)") (class "Default")
      (node (ref "J1") (pin "10") (pinfunction "MS_10") (pintype "passive"))
      (node (ref "R7") (pin "6") (pinfunction "2_6") (pintype "passive"))
    )
    (net (code "69") (name "Net-(J1C-MS)") (class "Default")
      (node (ref "J1") (pin "11") (pinfunction "MS_11") (pintype "passive"))
      (node (ref "R7") (pin "7") (pinfunction "2_7") (pintype "passive"))
    )
    (net (code "70") (name "Net-(J1D-MS)") (class "Default")
      (node (ref "J1") (pin "12") (pinfunction "MS_12") (pintype "passive"))
      (node (ref "R7") (pin "8") (pinfunction "2_8") (pintype "passive"))
    )
    (net (code "71") (name "Net-(J1E-MS)") (class "Default")
      (node (ref "J1") (pin "13") (pinfunction "MS_13") (pintype "passive"))
      (node (ref "R8") (pin "5") (pinfunction "2_5") (pintype "passive"))
    )
    (net (code "72") (name "Net-(J1F-MS)") (class "Default")
      (node (ref "J1") (pin "14") (pinfunction "MS_14") (pintype "passive"))
      (node (ref "R8") (pin "6") (pinfunction "2_6") (pintype "passive"))
    )
    (net (code "73") (name "Net-(J1G-MS)") (class "Default")
      (node (ref "J1") (pin "15") (pinfunction "MS_15") (pintype "passive"))
      (node (ref "R8") (pin "7") (pinfunction "2_7") (pintype "passive"))
    )
    (net (code "74") (name "Net-(J1H-MS)") (class "Default")
      (node (ref "J1") (pin "16") (pinfunction "MS_16") (pintype "passive"))
      (node (ref "R8") (pin "8") (pinfunction "2_8") (pintype "passive"))
    )
    (net (code "75") (name "Net-(J1I-MS)") (class "Default")
      (node (ref "J1") (pin "17") (pinfunction "MS_17") (pintype "passive"))
      (node (ref "R9") (pin "5") (pinfunction "2_5") (pintype "passive"))
    )
    (net (code "76") (name "Net-(J1J-MS)") (class "Default")
      (node (ref "J1") (pin "18") (pinfunction "MS_18") (pintype "passive"))
      (node (ref "R9") (pin "6") (pinfunction "2_6") (pintype "passive"))
    )
    (net (code "77") (name "Net-(J1K-MS)") (class "Default")
      (node (ref "J1") (pin "19") (pinfunction "MS_19") (pintype "passive"))
      (node (ref "R9") (pin "7") (pinfunction "2_7") (pintype "passive"))
    )
    (net (code "78") (name "Net-(J1M-MS)") (class "Default")
      (node (ref "J1") (pin "20") (pinfunction "MS_20") (pintype "passive"))
      (node (ref "R9") (pin "8") (pinfunction "2_8") (pintype "passive"))
    )
    (net (code "79") (name "Net-(J1N-MS)") (class "Default")
      (node (ref "J1") (pin "21") (pinfunction "MS_21") (pintype "passive"))
      (node (ref "R10") (pin "5") (pinfunction "2_5") (pintype "passive"))
    )
    (net (code "80") (name "Net-(J1O-MS)") (class "Default")
      (node (ref "J1") (pin "22") (pinfunction "MS_22") (pintype "passive"))
      (node (ref "R10") (pin "6") (pinfunction "2_6") (pintype "passive"))
    )
    (net (code "81") (name "Net-(J1P-MS)") (class "Default")
      (node (ref "J1") (pin "23") (pinfunction "MS_23") (pintype "passive"))
      (node (ref "R10") (pin "7") (pinfunction "2_7") (pintype "passive"))
    )
    (net (code "82") (name "Net-(J1Q-MS)") (class "Default")
      (node (ref "J1") (pin "24") (pinfunction "MS_24") (pintype "passive"))
      (node (ref "R10") (pin "8") (pinfunction "2_8") (pintype "passive"))
    )
    (net (code "83") (name "Net-(J1R-MS)") (class "Default")
      (node (ref "J1") (pin "25") (pinfunction "MS_25") (pintype "passive"))
      (node (ref "R11") (pin "5") (pinfunction "2_5") (pintype "passive"))
    )
    (net (code "84") (name "Net-(J1S-MS)") (class "Default")
      (node (ref "J1") (pin "26") (pinfunction "MS_26") (pintype "passive"))
      (node (ref "R11") (pin "6") (pinfunction "2_6") (pintype "passive"))
    )
    (net (code "85") (name "Net-(J1T-MS)") (class "Default")
      (node (ref "J1") (pin "27") (pinfunction "MS_27") (pintype "passive"))
      (node (ref "R11") (pin "7") (pinfunction "2_7") (pintype "passive"))
    )
    (net (code "86") (name "Net-(J1U-MS)") (class "Default")
      (node (ref "J1") (pin "28") (pinfunction "MS_28") (pintype "passive"))
      (node (ref "R11") (pin "8") (pinfunction "2_8") (pintype "passive"))
    )
    (net (code "87") (name "Net-(L1-2)") (class "Default")
      (node (ref "D1") (pin "A") (pinfunction "A_A") (pintype "passive"))
      (node (ref "L1") (pin "P$2") (pinfunction "2_P$2") (pintype "passive"))
      (node (ref "U4") (pin "1") (pinfunction "SW_1") (pintype "bidirectional"))
    )
    (net (code "88") (name "Net-(LED1-PadC)") (class "Default")
      (node (ref "LED1") (pin "C") (pinfunction "C_C") (pintype "passive"))
      (node (ref "R14") (pin "1") (pinfunction "1_1") (pintype "passive"))
    )
    (net (code "89") (name "Net-(LED2-PadC)") (class "Default")
      (node (ref "LED2") (pin "C") (pinfunction "C_C") (pintype "passive"))
      (node (ref "R19") (pin "1") (pinfunction "1_1") (pintype "passive"))
    )
    (net (code "90") (name "Net-(LED3-PadC)") (class "Default")
      (node (ref "LED3") (pin "C") (pinfunction "C_C") (pintype "passive"))
      (node (ref "R20") (pin "1") (pinfunction "1_1") (pintype "passive"))
    )
    (net (code "91") (name "Net-(Q1-D)") (class "Default")
      (node (ref "Q1") (pin "3") (pinfunction "D_3") (pintype "bidirectional"))
      (node (ref "R20") (pin "2") (pinfunction "2_2") (pintype "passive"))
    )
    (net (code "92") (name "Net-(Q1-G)") (class "Default")
      (node (ref "Q1") (pin "1") (pinfunction "G_1") (pintype "bidirectional"))
      (node (ref "R21") (pin "2") (pinfunction "2_2") (pintype "passive"))
    )
    (net (code "93") (name "Net-(R12B-1)") (class "Default")
      (node (ref "R12") (pin "2") (pinfunction "1_2") (pintype "passive"))
      (node (ref "U1") (pin "47") (pinfunction "VSYNC_47") (pintype "output"))
    )
    (net (code "94") (name "Net-(R12C-1)") (class "Default")
      (node (ref "R12") (pin "3") (pinfunction "1_3") (pintype "passive"))
      (node (ref "U1") (pin "46") (pinfunction "DE_46") (pintype "output"))
    )
    (net (code "95") (name "Net-(R12D-1)") (class "Default")
      (node (ref "R12") (pin "4") (pinfunction "1_4") (pintype "passive"))
      (node (ref "U1") (pin "44") (pinfunction "ODCK_44") (pintype "output"))
    )
    (net (code "96") (name "Net-(R15-Pad1)") (class "Default")
      (node (ref "R15") (pin "1") (pinfunction "1_1") (pintype "passive"))
      (node (ref "SJ3") (pin "1") (pinfunction "1_1") (pintype "passive"))
    )
    (net (code "97") (name "Net-(U1A-HSYNC)") (class "Default")
      (node (ref "R12") (pin "1") (pinfunction "1_1") (pintype "passive"))
      (node (ref "U1") (pin "48") (pinfunction "HSYNC_48") (pintype "output"))
    )
    (net (code "98") (name "Net-(U1A-OCK_INV)") (class "Default")
      (node (ref "R5") (pin "2") (pinfunction "2_2") (pintype "passive"))
      (node (ref "SJ1") (pin "1") (pinfunction "1_1") (pintype "passive"))
      (node (ref "U1") (pin "100") (pinfunction "OCK_INV_100") (pintype "input"))
    )
    (net (code "99") (name "Net-(U1A-RX0+)") (class "Default")
      (node (ref "U1") (pin "90") (pinfunction "RX0+_90") (pintype "input"))
      (node (ref "X1") (pin "7") (pinfunction "TX0+_7") (pintype "bidirectional"))
    )
    (net (code "100") (name "Net-(U1A-RX0-)") (class "Default")
      (node (ref "U1") (pin "91") (pinfunction "RX0-_91") (pintype "input"))
      (node (ref "X1") (pin "9") (pinfunction "TX0-_9") (pintype "bidirectional"))
    )
    (net (code "101") (name "Net-(U1A-RX1+)") (class "Default")
      (node (ref "U1") (pin "85") (pinfunction "RX1+_85") (pintype "input"))
      (node (ref "X1") (pin "4") (pinfunction "TX1+_4") (pintype "bidirectional"))
    )
    (net (code "102") (name "Net-(U1A-RX1-)") (class "Default")
      (node (ref "U1") (pin "86") (pinfunction "RX1-_86") (pintype "input"))
      (node (ref "X1") (pin "6") (pinfunction "TX1-_6") (pintype "bidirectional"))
    )
    (net (code "103") (name "Net-(U1A-RX2+)") (class "Default")
      (node (ref "U1") (pin "80") (pinfunction "RX2+_80") (pintype "input"))
      (node (ref "X1") (pin "1") (pinfunction "TX2+_1") (pintype "bidirectional"))
    )
    (net (code "104") (name "Net-(U1A-RX2-)") (class "Default")
      (node (ref "U1") (pin "81") (pinfunction "RX2-_81") (pintype "input"))
      (node (ref "X1") (pin "3") (pinfunction "TX2-_3") (pintype "bidirectional"))
    )
    (net (code "105") (name "Net-(U1A-RXC+)") (class "Default")
      (node (ref "U1") (pin "93") (pinfunction "RXC+_93") (pintype "input"))
      (node (ref "X1") (pin "10") (pinfunction "TXC+_10") (pintype "bidirectional"))
    )
    (net (code "106") (name "Net-(U1A-RXC-)") (class "Default")
      (node (ref "U1") (pin "94") (pinfunction "RXC-_94") (pintype "input"))
      (node (ref "X1") (pin "12") (pinfunction "TXC-_12") (pintype "bidirectional"))
    )
    (net (code "107") (name "Net-(U1A-ST)") (class "Default")
      (node (ref "R2") (pin "2") (pinfunction "2_2") (pintype "passive"))
      (node (ref "SJ2") (pin "2") (pinfunction "2_2") (pintype "passive"))
      (node (ref "U1") (pin "3") (pinfunction "ST_3") (pintype "input"))
    )
    (net (code "108") (name "Net-(U4-SHDN)") (class "Default")
      (node (ref "BACKLITEPWM") (pin "1") (pinfunction "1_1") (pintype "passive"))
      (node (ref "D3") (pin "A") (pinfunction "A_A") (pintype "passive"))
      (node (ref "R18") (pin "2") (pinfunction "2_2") (pintype "passive"))
      (node (ref "U4") (pin "4") (pinfunction "SHDN_4") (pintype "bidirectional"))
    )
    (net (code "109") (name "Net-(X1A-HOTPLUG)") (class "Default")
      (node (ref "R1") (pin "1") (pinfunction "1_1") (pintype "passive"))
      (node (ref "X1") (pin "19") (pinfunction "HOTPLUG_19") (pintype "bidirectional"))
    )
    (net (code "110") (name "VDD") (class "Default")
      (node (ref "C14") (pin "1") (pinfunction "1_1") (pintype "passive"))
      (node (ref "C15") (pin "1") (pinfunction "1_1") (pintype "passive"))
      (node (ref "C23") (pin "1") (pinfunction "1_1") (pintype "passive"))
      (node (ref "FB1") (pin "1") (pinfunction "P$1_1") (pintype "passive"))
      (node (ref "FB2") (pin "1") (pinfunction "P$1_1") (pintype "passive"))
      (node (ref "FB3") (pin "1") (pinfunction "P$1_1") (pintype "passive"))
      (node (ref "FB4") (pin "1") (pinfunction "P$1_1") (pintype "passive"))
      (node (ref "J1") (pin "4") (pinfunction "MS_4") (pintype "passive"))
      (node (ref "JP7") (pin "1") (pinfunction "1_1") (pintype "passive"))
      (node (ref "LED2") (pin "A") (pinfunction "A_A") (pintype "passive"))
      (node (ref "LED3") (pin "A") (pinfunction "A_A") (pintype "passive"))
      (node (ref "SJ4") (pin "1") (pinfunction "1_1") (pintype "passive"))
      (node (ref "U3") (pin "2") (pinfunction "OUT_2") (pintype "power_in"))
      (node (ref "U3") (pin "4") (pinfunction "OUT_4") (pintype "power_in"))
    )
    (net (code "111") (name "VDDIO") (class "Default")
      (node (ref "C2") (pin "1") (pinfunction "1_1") (pintype "passive"))
      (node (ref "C3") (pin "1") (pinfunction "1_1") (pintype "passive"))
      (node (ref "FB1") (pin "2") (pinfunction "P$2_2") (pintype "passive"))
      (node (ref "R2") (pin "1") (pinfunction "1_1") (pintype "passive"))
      (node (ref "SJ1") (pin "2") (pinfunction "2_2") (pintype "passive"))
      (node (ref "U1") (pin "38") (pinfunction "DVDD_38") (pintype "power_in"))
      (node (ref "U1") (pin "6") (pinfunction "DVDD_6") (pintype "power_in"))
      (node (ref "U1") (pin "67") (pinfunction "DVDD_67") (pintype "power_in"))
      (node (ref "U1") (pin "7") (pinfunction "#STAG_7") (pintype "input"))
      (node (ref "U1") (pin "99") (pinfunction "RSVD_99") (pintype "input"))
    )
    (net (code "112") (name "VIN") (class "Default")
      (node (ref "C12") (pin "1") (pinfunction "1_1") (pintype "passive"))
      (node (ref "C13") (pin "1") (pinfunction "1_1") (pintype "passive"))
      (node (ref "C16") (pin "2") (pinfunction "2_2") (pintype "passive"))
      (node (ref "C24") (pin "+") (pinfunction "+_+") (pintype "passive"))
      (node (ref "C25") (pin "1") (pinfunction "1_1") (pintype "passive"))
      (node (ref "JP6") (pin "1") (pinfunction "1_1") (pintype "passive"))
      (node (ref "L1") (pin "P$1") (pinfunction "1_P$1") (pintype "passive"))
      (node (ref "R18") (pin "1") (pinfunction "1_1") (pintype "passive"))
      (node (ref "U3") (pin "3") (pinfunction "IN_3") (pintype "power_in"))
      (node (ref "U4") (pin "5") (pinfunction "VIN_5") (pintype "bidirectional"))
      (node (ref "X2") (pin "VBUS") (pinfunction "VBUS_VBUS") (pintype "power_in"))
    )
    (net (code "113") (name "unconnected-(IC1-RX-Pad12)") (class "Default")
      (node (ref "IC1") (pin "12") (pinfunction "RX_12") (pintype "input"))
    )
    (net (code "114") (name "unconnected-(IC1-TX-Pad10)") (class "Default")
      (node (ref "IC1") (pin "10") (pinfunction "TX_10") (pintype "output"))
    )
    (net (code "115") (name "unconnected-(J1AC-MS-Pad35)") (class "Default")
      (node (ref "J1") (pin "35") (pinfunction "MS_35") (pintype "passive"))
    )
    (net (code "116") (name "unconnected-(U1A-EXTRES-Pad96)") (class "Default")
      (node (ref "U1") (pin "96") (pinfunction "EXTRES_96") (pintype "input"))
    )
    (net (code "117") (name "unconnected-(U1A-QO0-Pad49)") (class "Default")
      (node (ref "U1") (pin "49") (pinfunction "QO0_49") (pintype "output"))
    )
    (net (code "118") (name "unconnected-(U1A-QO1-Pad50)") (class "Default")
      (node (ref "U1") (pin "50") (pinfunction "QO1_50") (pintype "output"))
    )
    (net (code "119") (name "unconnected-(U1A-QO2-Pad51)") (class "Default")
      (node (ref "U1") (pin "51") (pinfunction "QO2_51") (pintype "output"))
    )
    (net (code "120") (name "unconnected-(U1A-QO3-Pad52)") (class "Default")
      (node (ref "U1") (pin "52") (pinfunction "QO3_52") (pintype "output"))
    )
    (net (code "121") (name "unconnected-(U1A-QO4-Pad53)") (class "Default")
      (node (ref "U1") (pin "53") (pinfunction "QO4_53") (pintype "output"))
    )
    (net (code "122") (name "unconnected-(U1A-QO5-Pad54)") (class "Default")
      (node (ref "U1") (pin "54") (pinfunction "QO5_54") (pintype "output"))
    )
    (net (code "123") (name "unconnected-(U1A-QO6-Pad55)") (class "Default")
      (node (ref "U1") (pin "55") (pinfunction "QO6_55") (pintype "output"))
    )
    (net (code "124") (name "unconnected-(U1A-QO7-Pad56)") (class "Default")
      (node (ref "U1") (pin "56") (pinfunction "QO7_56") (pintype "output"))
    )
    (net (code "125") (name "unconnected-(U1A-QO8-Pad59)") (class "Default")
      (node (ref "U1") (pin "59") (pinfunction "QO8_59") (pintype "output"))
    )
    (net (code "126") (name "unconnected-(U1A-QO9-Pad60)") (class "Default")
      (node (ref "U1") (pin "60") (pinfunction "QO9_60") (pintype "output"))
    )
    (net (code "127") (name "unconnected-(U1A-QO10-Pad61)") (class "Default")
      (node (ref "U1") (pin "61") (pinfunction "QO10_61") (pintype "output"))
    )
    (net (code "128") (name "unconnected-(U1A-QO11-Pad62)") (class "Default")
      (node (ref "U1") (pin "62") (pinfunction "QO11_62") (pintype "output"))
    )
    (net (code "129") (name "unconnected-(U1A-QO12-Pad63)") (class "Default")
      (node (ref "U1") (pin "63") (pinfunction "QO12_63") (pintype "output"))
    )
    (net (code "130") (name "unconnected-(U1A-QO13-Pad64)") (class "Default")
      (node (ref "U1") (pin "64") (pinfunction "QO13_64") (pintype "output"))
    )
    (net (code "131") (name "unconnected-(U1A-QO14-Pad65)") (class "Default")
      (node (ref "U1") (pin "65") (pinfunction "QO14_65") (pintype "output"))
    )
    (net (code "132") (name "unconnected-(U1A-QO15-Pad66)") (class "Default")
      (node (ref "U1") (pin "66") (pinfunction "QO15_66") (pintype "output"))
    )
    (net (code "133") (name "unconnected-(U1A-QO16-Pad69)") (class "Default")
      (node (ref "U1") (pin "69") (pinfunction "QO16_69") (pintype "output"))
    )
    (net (code "134") (name "unconnected-(U1A-QO17-Pad70)") (class "Default")
      (node (ref "U1") (pin "70") (pinfunction "QO17_70") (pintype "output"))
    )
    (net (code "135") (name "unconnected-(U1A-QO18-Pad71)") (class "Default")
      (node (ref "U1") (pin "71") (pinfunction "QO18_71") (pintype "output"))
    )
    (net (code "136") (name "unconnected-(U1A-QO19-Pad72)") (class "Default")
      (node (ref "U1") (pin "72") (pinfunction "QO19_72") (pintype "output"))
    )
    (net (code "137") (name "unconnected-(U1A-QO20-Pad73)") (class "Default")
      (node (ref "U1") (pin "73") (pinfunction "QO20_73") (pintype "output"))
    )
    (net (code "138") (name "unconnected-(U1A-QO21-Pad74)") (class "Default")
      (node (ref "U1") (pin "74") (pinfunction "QO21_74") (pintype "output"))
    )
    (net (code "139") (name "unconnected-(U1A-QO22-Pad75)") (class "Default")
      (node (ref "U1") (pin "75") (pinfunction "QO22_75") (pintype "output"))
    )
    (net (code "140") (name "unconnected-(U1A-QO23-Pad77)") (class "Default")
      (node (ref "U1") (pin "77") (pinfunction "QO23_77") (pintype "output"))
    )
    (net (code "141") (name "unconnected-(X1A-CEC-Pad13)") (class "Default")
      (node (ref "X1") (pin "13") (pinfunction "CEC_13") (pintype "bidirectional"))
    )
    (net (code "142") (name "unconnected-(X1A-UTILITY-Pad14)") (class "Default")
      (node (ref "X1") (pin "14") (pinfunction "UTILITY_14") (pintype "bidirectional"))
    )
    (net (code "143") (name "unconnected-(X2-PadID)") (class "Default")
      (node (ref "X2") (pin "ID") (pinfunction "ID_ID") (pintype "bidirectional"))
    )
  )
)
